# PFC_Method_Lighting_V1_1.net
KiCad netlist of a schematic drawn in EAGLE
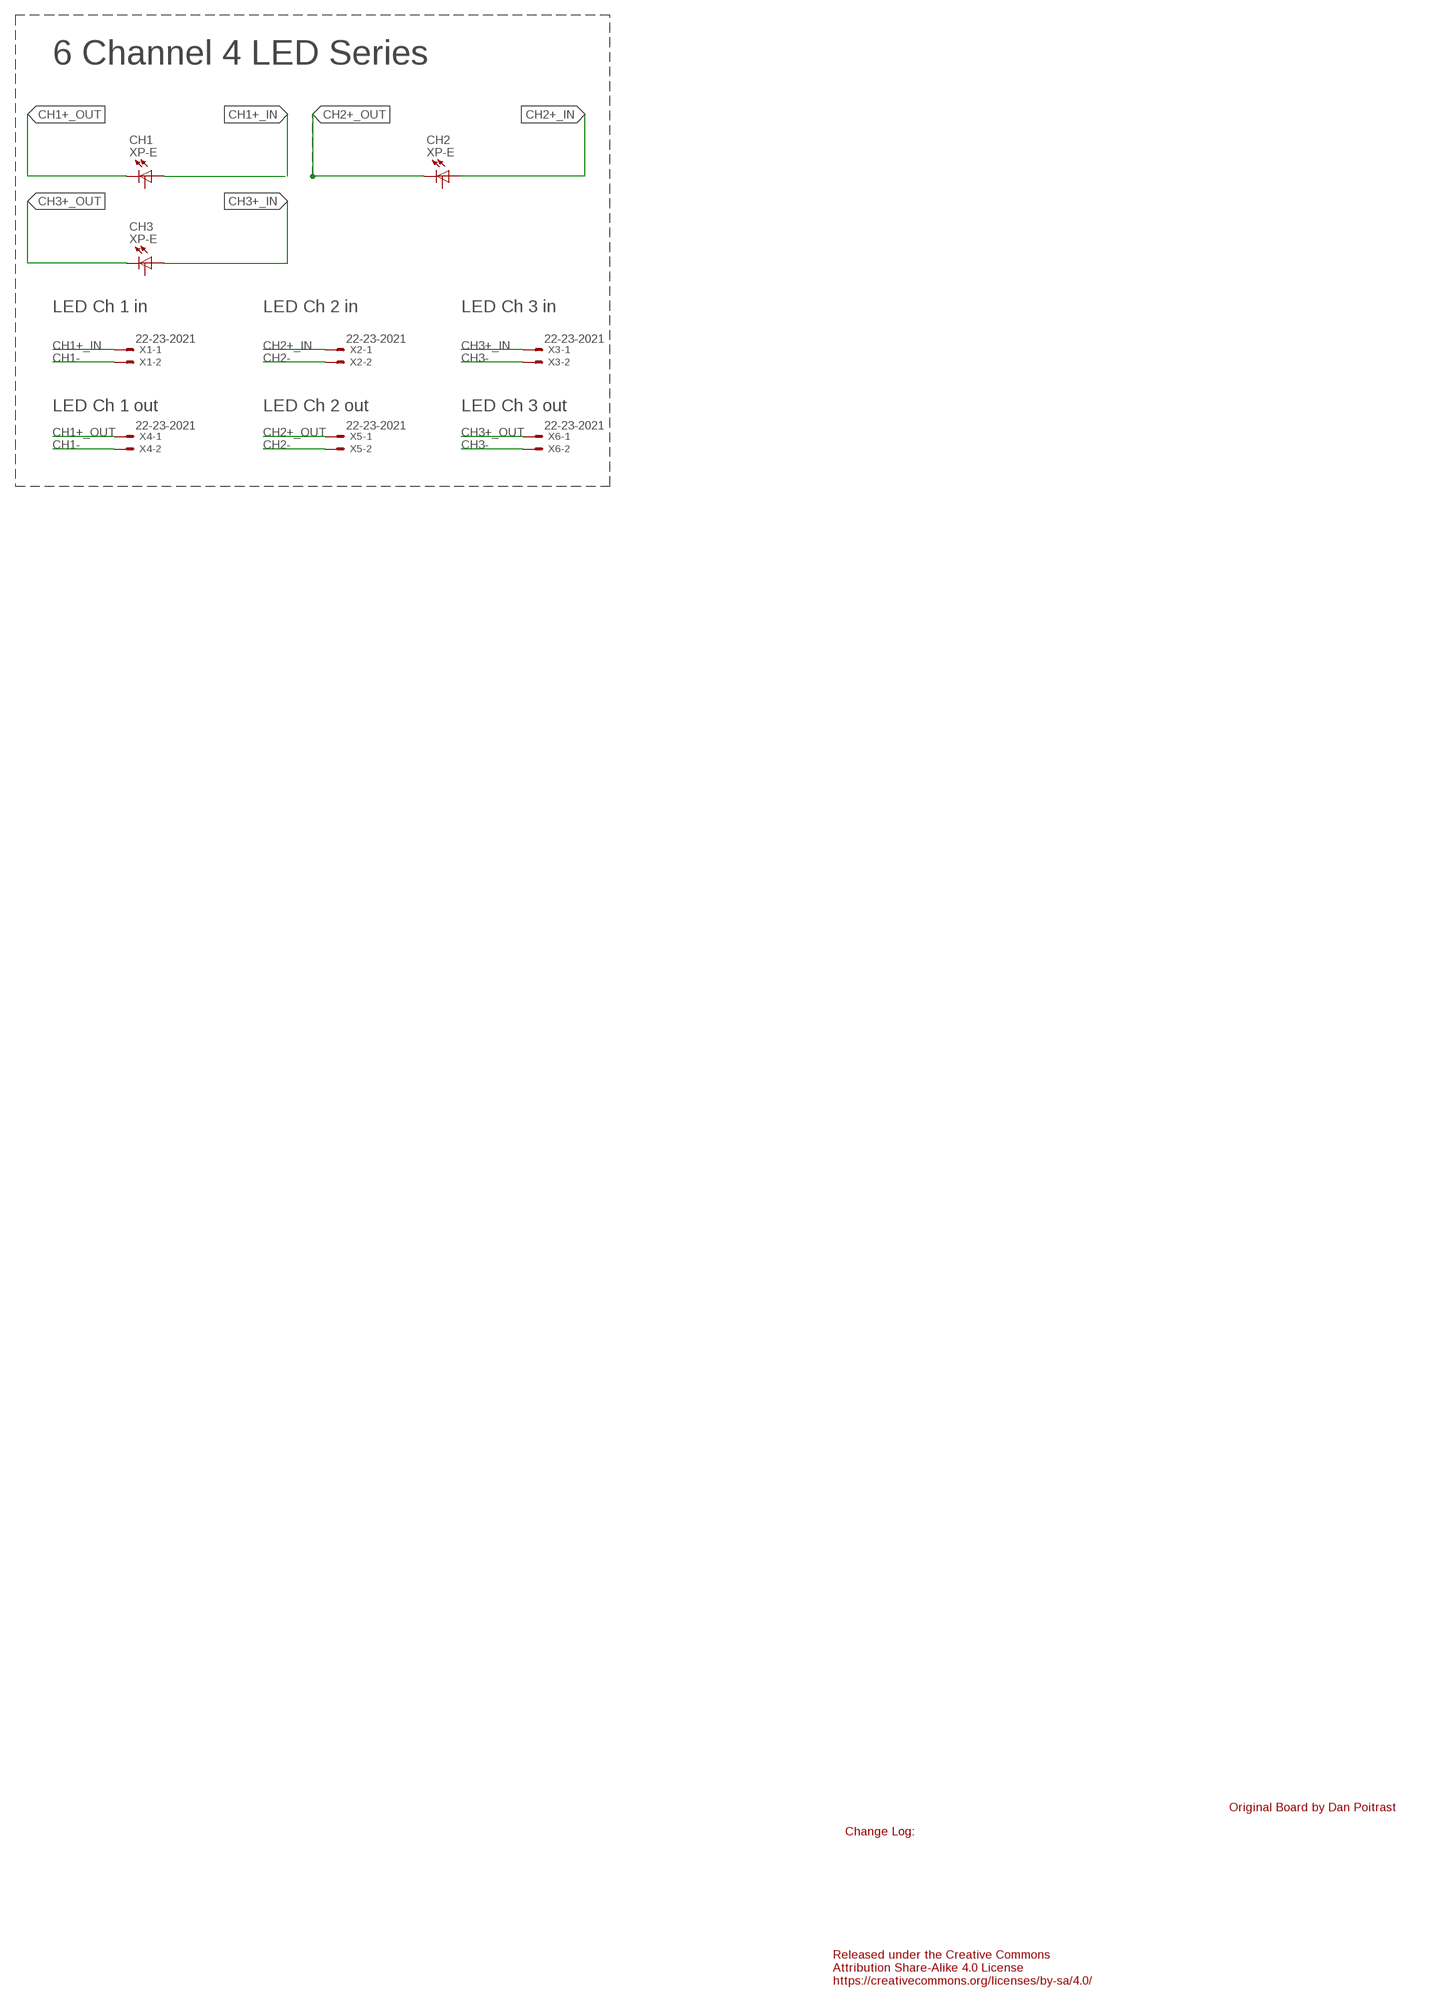
[diagram p0: schematic, sheet 1]

(export (version "E")
  (design (tool "Eeschema 10.0.6"))
  (components
    (comp (ref "CH1")
      (value "XP-E")
      (footprint "eagle-import:CREE-XLAMP-XP-E")
      (libsource (lib "eagle-import") (part "LED_W/THERM-XP-E"))
    )
    (comp (ref "CH2")
      (value "XP-E")
      (footprint "eagle-import:CREE-XLAMP-XP-E")
      (libsource (lib "eagle-import") (part "LED_W/THERM-XP-E"))
    )
    (comp (ref "CH3")
      (value "XP-E")
      (footprint "eagle-import:CREE-XLAMP-XP-E")
      (libsource (lib "eagle-import") (part "LED_W/THERM-XP-E"))
    )
    (comp (ref "X1")
      (value "22-23-2021")
      (footprint "eagle-import:22-23-2021")
      (fields (field (name "MF") "MOLEX"))
      (libsource (lib "eagle-import") (part "22-23-2021"))
    )
    (comp (ref "X2")
      (value "22-23-2021")
      (footprint "eagle-import:22-23-2021")
      (fields (field (name "MF") "MOLEX"))
      (libsource (lib "eagle-import") (part "22-23-2021"))
    )
    (comp (ref "X3")
      (value "22-23-2021")
      (footprint "eagle-import:22-23-2021")
      (fields (field (name "MF") "MOLEX"))
      (libsource (lib "eagle-import") (part "22-23-2021"))
    )
    (comp (ref "X4")
      (value "22-23-2021")
      (footprint "eagle-import:22-23-2021")
      (fields (field (name "MF") "MOLEX"))
      (libsource (lib "eagle-import") (part "22-23-2021"))
    )
    (comp (ref "X5")
      (value "22-23-2021")
      (footprint "eagle-import:22-23-2021")
      (fields (field (name "MF") "MOLEX"))
      (libsource (lib "eagle-import") (part "22-23-2021"))
    )
    (comp (ref "X6")
      (value "22-23-2021")
      (footprint "eagle-import:22-23-2021")
      (fields (field (name "MF") "MOLEX"))
      (libsource (lib "eagle-import") (part "22-23-2021"))
    )
  )
  (nets
    (net (code "1") (name "/CH1-") (class "Default")
      (node (ref "X1") (pin "2") (pinfunction "S_2") (pintype "passive"))
      (node (ref "X4") (pin "2") (pinfunction "S_2") (pintype "passive"))
    )
    (net (code "2") (name "/CH2-") (class "Default")
      (node (ref "X2") (pin "2") (pinfunction "S_2") (pintype "passive"))
      (node (ref "X5") (pin "2") (pinfunction "S_2") (pintype "passive"))
    )
    (net (code "3") (name "/CH3-") (class "Default")
      (node (ref "X3") (pin "2") (pinfunction "S_2") (pintype "passive"))
      (node (ref "X6") (pin "2") (pinfunction "S_2") (pintype "passive"))
    )
    (net (code "4") (name "CH1+_IN") (class "Default")
      (node (ref "CH1") (pin "A") (pinfunction "A_A") (pintype "passive"))
      (node (ref "CH1") (pin "A@1") (pinfunction "A_A@1") (pintype "passive"))
      (node (ref "X1") (pin "1") (pinfunction "S_1") (pintype "passive"))
    )
    (net (code "5") (name "CH1+_OUT") (class "Default")
      (node (ref "CH1") (pin "C") (pinfunction "C_C") (pintype "passive"))
      (node (ref "CH1") (pin "C@1") (pinfunction "C_C@1") (pintype "passive"))
      (node (ref "X4") (pin "1") (pinfunction "S_1") (pintype "passive"))
    )
    (net (code "6") (name "CH2+_IN") (class "Default")
      (node (ref "CH2") (pin "A") (pinfunction "A_A") (pintype "passive"))
      (node (ref "CH2") (pin "A@1") (pinfunction "A_A@1") (pintype "passive"))
      (node (ref "X2") (pin "1") (pinfunction "S_1") (pintype "passive"))
    )
    (net (code "7") (name "CH2+_OUT") (class "Default")
      (node (ref "CH2") (pin "C") (pinfunction "C_C") (pintype "passive"))
      (node (ref "CH2") (pin "C@1") (pinfunction "C_C@1") (pintype "passive"))
      (node (ref "X5") (pin "1") (pinfunction "S_1") (pintype "passive"))
    )
    (net (code "8") (name "CH3+_IN") (class "Default")
      (node (ref "CH3") (pin "A") (pinfunction "A_A") (pintype "passive"))
      (node (ref "CH3") (pin "A@1") (pinfunction "A_A@1") (pintype "passive"))
      (node (ref "X3") (pin "1") (pinfunction "S_1") (pintype "passive"))
    )
    (net (code "9") (name "CH3+_OUT") (class "Default")
      (node (ref "CH3") (pin "C") (pinfunction "C_C") (pintype "passive"))
      (node (ref "CH3") (pin "C@1") (pinfunction "C_C@1") (pintype "passive"))
      (node (ref "X6") (pin "1") (pinfunction "S_1") (pintype "passive"))
    )
    (net (code "10") (name "unconnected-(CH1-PadTHERM)") (class "Default")
      (node (ref "CH1") (pin "THERM") (pinfunction "THERM_THERM") (pintype "bidirectional"))
    )
    (net (code "11") (name "unconnected-(CH2-PadTHERM)") (class "Default")
      (node (ref "CH2") (pin "THERM") (pinfunction "THERM_THERM") (pintype "bidirectional"))
    )
    (net (code "12") (name "unconnected-(CH3-PadTHERM)") (class "Default")
      (node (ref "CH3") (pin "THERM") (pinfunction "THERM_THERM") (pintype "bidirectional"))
    )
  )
)
